# CircularControllerSensors.net
KiCad netlist of a schematic drawn in EAGLE
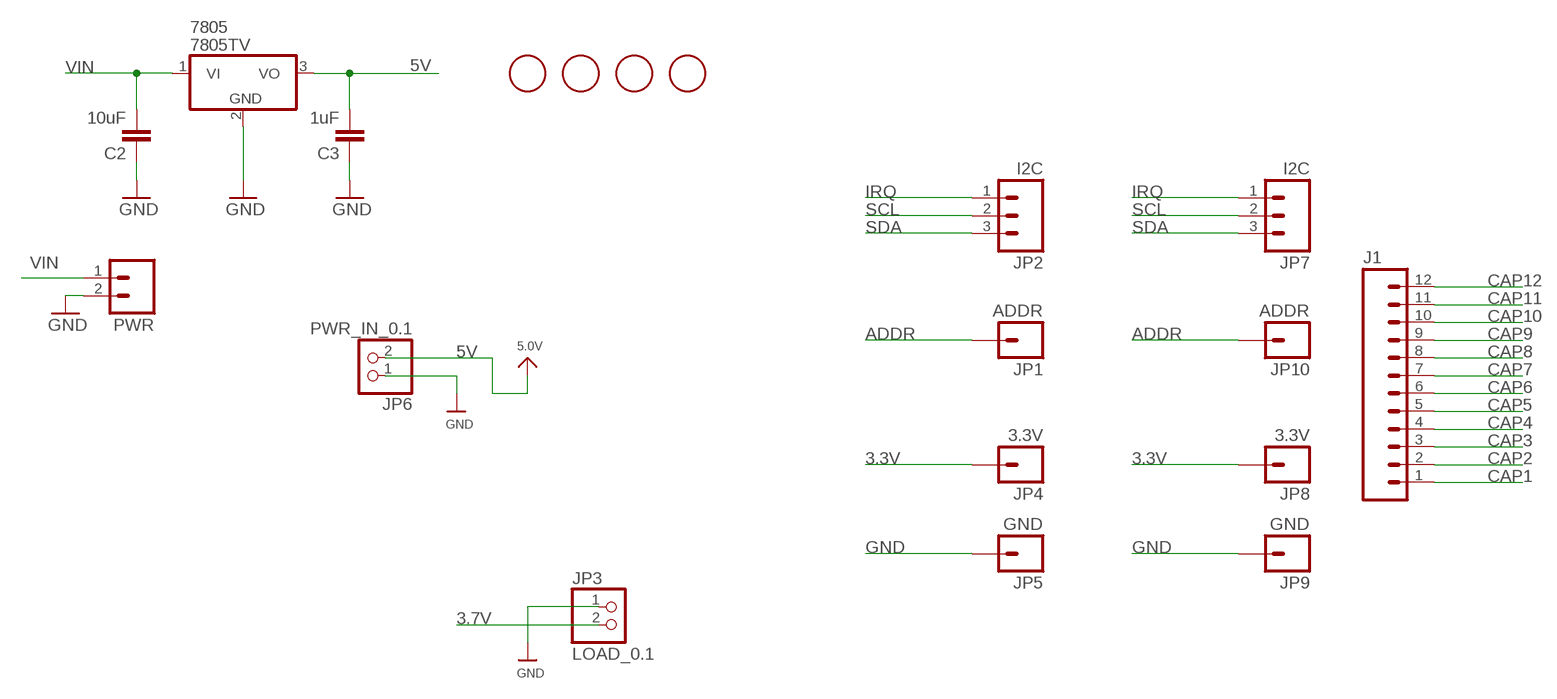
[diagram p0: schematic, sheet 1]

(export (version "E")
  (design (tool "Eeschema 10.0.6"))
  (components
    (comp (ref "7805")
      (value "7805TV")
      (footprint "eagle-import:TO220V")
      (libsource (lib "eagle-import") (part "78TV05"))
    )
    (comp (ref "C2")
      (value "10uF")
      (footprint "eagle-import:1206")
      (libsource (lib "eagle-import") (part "10UF-6.3V-20%(1206)"))
    )
    (comp (ref "C3")
      (value "1uF")
      (footprint "eagle-import:1206")
      (libsource (lib "eagle-import") (part "10UF-6.3V-20%(1206)"))
    )
    (comp (ref "J1")
      (value "M12PTH")
      (footprint "eagle-import:1X12")
      (libsource (lib "eagle-import") (part "M12PTH"))
    )
    (comp (ref "JP1")
      (value "ADDR")
      (footprint "eagle-import:1X01")
      (libsource (lib "eagle-import") (part "M01PTH"))
    )
    (comp (ref "JP2")
      (value "I2C")
      (footprint "eagle-import:1X03")
      (libsource (lib "eagle-import") (part "M03PTH"))
    )
    (comp (ref "JP3")
      (value "LOAD_0.1")
      (footprint "eagle-import:1X02_OVAL")
      (libsource (lib "eagle-import") (part "HEADER-1X2"))
    )
    (comp (ref "JP4")
      (value "3.3V")
      (footprint "eagle-import:1X01")
      (libsource (lib "eagle-import") (part "M01PTH"))
    )
    (comp (ref "JP5")
      (value "GND")
      (footprint "eagle-import:1X01")
      (libsource (lib "eagle-import") (part "M01PTH"))
    )
    (comp (ref "JP6")
      (value "PWR_IN_0.1")
      (footprint "eagle-import:1X02_OVAL")
      (libsource (lib "eagle-import") (part "HEADER-1X2"))
    )
    (comp (ref "JP7")
      (value "I2C")
      (footprint "eagle-import:1X03")
      (libsource (lib "eagle-import") (part "M03PTH"))
    )
    (comp (ref "JP8")
      (value "3.3V")
      (footprint "eagle-import:1X01")
      (libsource (lib "eagle-import") (part "M01PTH"))
    )
    (comp (ref "JP9")
      (value "GND")
      (footprint "eagle-import:1X01")
      (libsource (lib "eagle-import") (part "M01PTH"))
    )
    (comp (ref "JP10")
      (value "ADDR")
      (footprint "eagle-import:1X01")
      (libsource (lib "eagle-import") (part "M01PTH"))
    )
    (comp (ref "PWR")
      (value "M025MM")
      (footprint "eagle-import:SCREWTERMINAL-5MM-2")
      (libsource (lib "eagle-import") (part "M025MM"))
    )
    (comp (ref "U$11")
      (value "MOUNTINGHOLE2.0")
      (footprint "eagle-import:MOUNTINGHOLE_2.0_PLATED")
      (libsource (lib "eagle-import") (part "MOUNTINGHOLE2.0"))
    )
    (comp (ref "U$16")
      (value "MOUNTINGHOLE2.0")
      (footprint "eagle-import:MOUNTINGHOLE_2.0_PLATED")
      (libsource (lib "eagle-import") (part "MOUNTINGHOLE2.0"))
    )
    (comp (ref "U$18")
      (value "MOUNTINGHOLE2.0")
      (footprint "eagle-import:MOUNTINGHOLE_2.0_PLATED")
      (libsource (lib "eagle-import") (part "MOUNTINGHOLE2.0"))
    )
    (comp (ref "U$19")
      (value "MOUNTINGHOLE2.0")
      (footprint "eagle-import:MOUNTINGHOLE_2.0_PLATED")
      (libsource (lib "eagle-import") (part "MOUNTINGHOLE2.0"))
    )
  )
  (nets
    (net (code "1") (name "/3.3V") (class "Default")
      (node (ref "JP4") (pin "1") (pinfunction "1_1") (pintype "passive"))
      (node (ref "JP8") (pin "1") (pinfunction "1_1") (pintype "passive"))
    )
    (net (code "2") (name "/3.7V") (class "Default")
      (node (ref "JP3") (pin "2") (pinfunction "2_2") (pintype "passive"))
    )
    (net (code "3") (name "/ADDR") (class "Default")
      (node (ref "JP1") (pin "1") (pinfunction "1_1") (pintype "passive"))
      (node (ref "JP10") (pin "1") (pinfunction "1_1") (pintype "passive"))
    )
    (net (code "4") (name "/CAP1") (class "Default")
      (node (ref "J1") (pin "1") (pinfunction "1_1") (pintype "passive"))
    )
    (net (code "5") (name "/CAP2") (class "Default")
      (node (ref "J1") (pin "2") (pinfunction "2_2") (pintype "passive"))
    )
    (net (code "6") (name "/CAP3") (class "Default")
      (node (ref "J1") (pin "3") (pinfunction "3_3") (pintype "passive"))
    )
    (net (code "7") (name "/CAP4") (class "Default")
      (node (ref "J1") (pin "4") (pinfunction "4_4") (pintype "passive"))
    )
    (net (code "8") (name "/CAP5") (class "Default")
      (node (ref "J1") (pin "5") (pinfunction "5_5") (pintype "passive"))
    )
    (net (code "9") (name "/CAP6") (class "Default")
      (node (ref "J1") (pin "6") (pinfunction "6_6") (pintype "passive"))
    )
    (net (code "10") (name "/CAP7") (class "Default")
      (node (ref "J1") (pin "7") (pinfunction "7_7") (pintype "passive"))
    )
    (net (code "11") (name "/CAP8") (class "Default")
      (node (ref "J1") (pin "8") (pinfunction "8_8") (pintype "passive"))
    )
    (net (code "12") (name "/CAP9") (class "Default")
      (node (ref "J1") (pin "9") (pinfunction "9_9") (pintype "passive"))
    )
    (net (code "13") (name "/CAP10") (class "Default")
      (node (ref "J1") (pin "10") (pinfunction "10_10") (pintype "passive"))
    )
    (net (code "14") (name "/CAP11") (class "Default")
      (node (ref "J1") (pin "11") (pinfunction "11_11") (pintype "passive"))
    )
    (net (code "15") (name "/CAP12") (class "Default")
      (node (ref "J1") (pin "12") (pinfunction "12_12") (pintype "passive"))
    )
    (net (code "16") (name "/IRQ") (class "Default")
      (node (ref "JP2") (pin "1") (pinfunction "1_1") (pintype "passive"))
      (node (ref "JP7") (pin "1") (pinfunction "1_1") (pintype "passive"))
    )
    (net (code "17") (name "/SCL") (class "Default")
      (node (ref "JP2") (pin "2") (pinfunction "2_2") (pintype "passive"))
      (node (ref "JP7") (pin "2") (pinfunction "2_2") (pintype "passive"))
    )
    (net (code "18") (name "/SDA") (class "Default")
      (node (ref "JP2") (pin "3") (pinfunction "3_3") (pintype "passive"))
      (node (ref "JP7") (pin "3") (pinfunction "3_3") (pintype "passive"))
    )
    (net (code "19") (name "/VIN") (class "Default")
      (node (ref "7805") (pin "1") (pinfunction "VI_1") (pintype "input"))
      (node (ref "C2") (pin "2") (pinfunction "2_2") (pintype "passive"))
      (node (ref "PWR") (pin "1") (pinfunction "1_1") (pintype "passive"))
    )
    (net (code "20") (name "5.0V") (class "Default")
      (node (ref "7805") (pin "3") (pinfunction "VO_3") (pintype "passive"))
      (node (ref "C3") (pin "2") (pinfunction "2_2") (pintype "passive"))
      (node (ref "JP6") (pin "2") (pinfunction "2_2") (pintype "passive"))
    )
    (net (code "21") (name "GND") (class "Default")
      (node (ref "7805") (pin "2") (pinfunction "GND_2") (pintype "passive"))
      (node (ref "C2") (pin "1") (pinfunction "1_1") (pintype "passive"))
      (node (ref "C3") (pin "1") (pinfunction "1_1") (pintype "passive"))
      (node (ref "JP3") (pin "1") (pinfunction "1_1") (pintype "passive"))
      (node (ref "JP5") (pin "1") (pinfunction "1_1") (pintype "passive"))
      (node (ref "JP6") (pin "1") (pinfunction "1_1") (pintype "passive"))
      (node (ref "JP9") (pin "1") (pinfunction "1_1") (pintype "passive"))
      (node (ref "PWR") (pin "2") (pinfunction "2_2") (pintype "passive"))
    )
  )
)
